# 1-Schematic_5G23_copy.net
KiCad netlist of a schematic drawn in EasyEDA
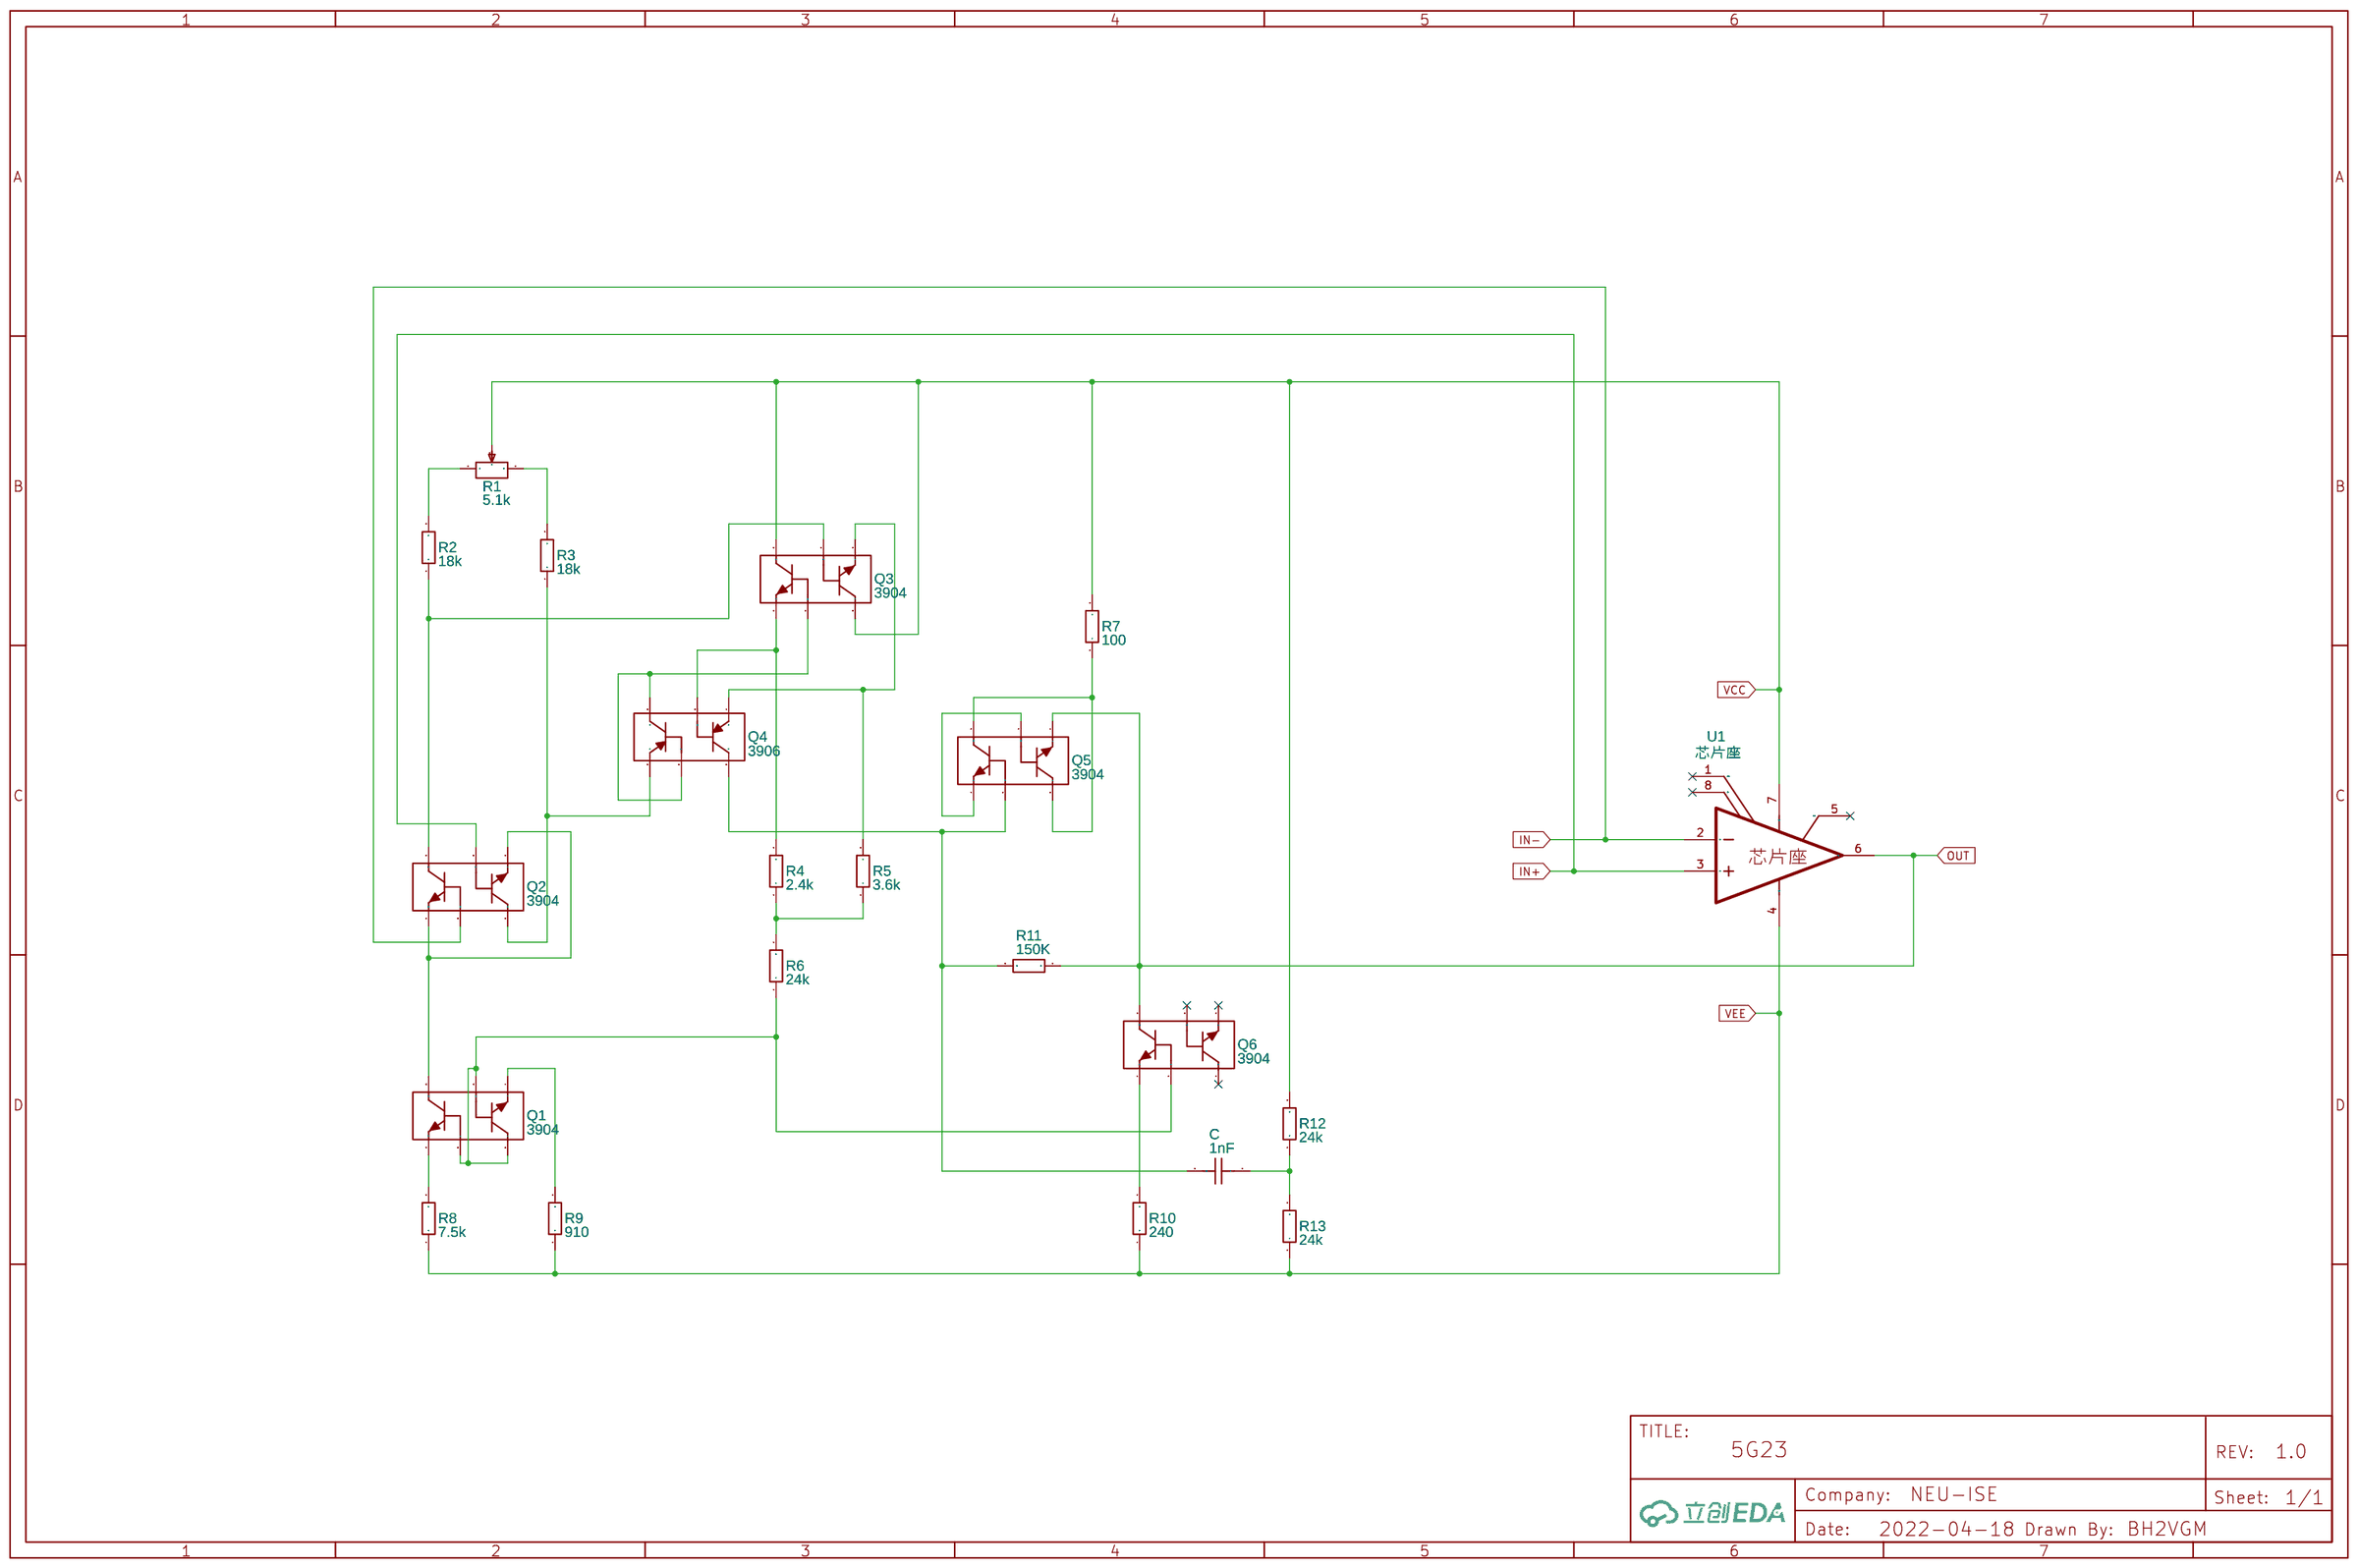
[diagram p0: schematic sheet]

(export (version "E")
  (design (tool "Eeschema 10.0.6"))
  (components
    (comp (ref "C")
      (value "1nF")
      (fields
        (field (name "BOM_Manufacturer Part") "1nF-C0603")
        (field (name "BOM_Supplier Part") "C2940049")
      )
      (libsource (lib "") (part "1NF-C0603"))
    )
    (comp (ref "Q1")
      (value "3904")
      (fields
        (field (name "BOM_Manufacturer Part") "MMDT3904-7-F")
        (field (name "BOM_Supplier Part") "C83572")
      )
      (libsource (lib "") (part "MMDT3904"))
    )
    (comp (ref "Q2")
      (value "3904")
      (fields
        (field (name "BOM_Manufacturer Part") "MMDT3904-7-F")
        (field (name "BOM_Supplier Part") "C83572")
      )
      (libsource (lib "") (part "MMDT3904"))
    )
    (comp (ref "Q3")
      (value "3904")
      (fields
        (field (name "BOM_Manufacturer Part") "MMDT3904-7-F")
        (field (name "BOM_Supplier Part") "C83572")
      )
      (libsource (lib "") (part "MMDT3904"))
    )
    (comp (ref "Q4")
      (value "3906")
      (fields
        (field (name "BOM_Manufacturer Part") "MMDT3906-TP")
        (field (name "BOM_Supplier Part") "C779248")
      )
      (libsource (lib "") (part "MMDT3906"))
    )
    (comp (ref "Q5")
      (value "3904")
      (fields
        (field (name "BOM_Manufacturer Part") "MMDT3904-7-F")
        (field (name "BOM_Supplier Part") "C83572")
      )
      (libsource (lib "") (part "MMDT3904"))
    )
    (comp (ref "Q6")
      (value "3904")
      (fields
        (field (name "BOM_Manufacturer Part") "MMDT3904-7-F")
        (field (name "BOM_Supplier Part") "C83572")
      )
      (libsource (lib "") (part "MMDT3904"))
    )
    (comp (ref "R1")
      (value "5.1k")
      (fields
        (field (name "BOM_Manufacturer Part") "VG039NCHXTB204")
        (field (name "BOM_Supplier Part") "C128551")
      )
      (libsource (lib "") (part "VG039NCHXTB204"))
    )
    (comp (ref "R2")
      (value "18k")
      (fields (field (name "BOM_Manufacturer Part") "0805") (field (name "BOM_Supplier Part") "C9900012715"))
      (libsource (lib "") (part "0805"))
    )
    (comp (ref "R3")
      (value "18k")
      (fields (field (name "BOM_Manufacturer Part") "0805") (field (name "BOM_Supplier Part") "C9900012715"))
      (libsource (lib "") (part "0805"))
    )
    (comp (ref "R4")
      (value "2.4k")
      (fields (field (name "BOM_Manufacturer Part") "0805") (field (name "BOM_Supplier Part") "C9900012715"))
      (libsource (lib "") (part "0805"))
    )
    (comp (ref "R5")
      (value "3.6k")
      (fields (field (name "BOM_Manufacturer Part") "0805") (field (name "BOM_Supplier Part") "C9900012715"))
      (libsource (lib "") (part "0805"))
    )
    (comp (ref "R6")
      (value "24k")
      (fields (field (name "BOM_Manufacturer Part") "0805") (field (name "BOM_Supplier Part") "C9900012715"))
      (libsource (lib "") (part "0805"))
    )
    (comp (ref "R7")
      (value "100")
      (fields (field (name "BOM_Manufacturer Part") "0805") (field (name "BOM_Supplier Part") "C9900012715"))
      (libsource (lib "") (part "0805"))
    )
    (comp (ref "R8")
      (value "7.5k")
      (fields (field (name "BOM_Manufacturer Part") "0805") (field (name "BOM_Supplier Part") "C9900012715"))
      (libsource (lib "") (part "0805"))
    )
    (comp (ref "R9")
      (value "910")
      (fields (field (name "BOM_Manufacturer Part") "0805") (field (name "BOM_Supplier Part") "C9900012715"))
      (libsource (lib "") (part "0805"))
    )
    (comp (ref "R10")
      (value "240")
      (fields (field (name "BOM_Manufacturer Part") "0805") (field (name "BOM_Supplier Part") "C9900012715"))
      (libsource (lib "") (part "0805"))
    )
    (comp (ref "R11")
      (value "150K")
      (fields (field (name "BOM_Manufacturer Part") "0805") (field (name "BOM_Supplier Part") "C9900012715"))
      (libsource (lib "") (part "0805_1"))
    )
    (comp (ref "R12")
      (value "24k")
      (fields (field (name "BOM_Manufacturer Part") "0805") (field (name "BOM_Supplier Part") "C9900012715"))
      (libsource (lib "") (part "0805"))
    )
    (comp (ref "R13")
      (value "24k")
      (fields (field (name "BOM_Manufacturer Part") "0805") (field (name "BOM_Supplier Part") "C9900012715"))
      (libsource (lib "") (part "0805"))
    )
    (comp (ref "U1")
      (value "芯片座")
      (fields (field (name "BOM_Manufacturer Part") "UA741CDR") (field (name "BOM_Supplier Part") "C2057458"))
      (libsource (lib "") (part "UA741CP"))
    )
  )
  (nets
    (net (code "1") (name "IN+") (class "Default")
      (node (ref "Q2") (pin "5") (pinfunction "B_5") (pintype "unspecified"))
      (node (ref "U1") (pin "3") (pinfunction "+IN_3") (pintype "unspecified"))
    )
    (net (code "2") (name "IN-") (class "Default")
      (node (ref "Q2") (pin "2") (pinfunction "B_2") (pintype "unspecified"))
      (node (ref "U1") (pin "2") (pinfunction "-IN_2") (pintype "unspecified"))
    )
    (net (code "3") (name "Net-(C-Pad1)") (class "Default")
      (node (ref "C") (pin "1") (pinfunction "1_1") (pintype "unspecified"))
      (node (ref "Q4") (pin "3") (pinfunction "C_3") (pintype "unspecified"))
      (node (ref "Q5") (pin "2") (pinfunction "B_2") (pintype "unspecified"))
      (node (ref "R11") (pin "2") (pinfunction "2_2") (pintype "unspecified"))
    )
    (net (code "4") (name "Net-(C-Pad2)") (class "Default")
      (node (ref "C") (pin "2") (pinfunction "2_2") (pintype "unspecified"))
      (node (ref "R12") (pin "1") (pinfunction "1_1") (pintype "unspecified"))
      (node (ref "R13") (pin "2") (pinfunction "2_2") (pintype "unspecified"))
    )
    (net (code "5") (name "Net-(Q1-B-Pad2)") (class "Default")
      (node (ref "Q1") (pin "2") (pinfunction "B_2") (pintype "unspecified"))
      (node (ref "Q1") (pin "3") (pinfunction "C_3") (pintype "unspecified"))
      (node (ref "Q1") (pin "5") (pinfunction "B_5") (pintype "unspecified"))
      (node (ref "Q6") (pin "2") (pinfunction "B_2") (pintype "unspecified"))
      (node (ref "R6") (pin "1") (pinfunction "1_1") (pintype "unspecified"))
    )
    (net (code "6") (name "Net-(Q1-C-Pad6)") (class "Default")
      (node (ref "Q1") (pin "6") (pinfunction "C_6") (pintype "unspecified"))
      (node (ref "Q2") (pin "1") (pinfunction "E_1") (pintype "unspecified"))
      (node (ref "Q2") (pin "4") (pinfunction "E_4") (pintype "unspecified"))
    )
    (net (code "7") (name "Net-(Q1-E-Pad1)") (class "Default")
      (node (ref "Q1") (pin "1") (pinfunction "E_1") (pintype "unspecified"))
      (node (ref "R8") (pin "2") (pinfunction "2_2") (pintype "unspecified"))
    )
    (net (code "8") (name "Net-(Q1-E-Pad4)") (class "Default")
      (node (ref "Q1") (pin "4") (pinfunction "E_4") (pintype "unspecified"))
      (node (ref "R9") (pin "2") (pinfunction "2_2") (pintype "unspecified"))
    )
    (net (code "9") (name "Net-(Q2-C-Pad3)") (class "Default")
      (node (ref "Q2") (pin "3") (pinfunction "C_3") (pintype "unspecified"))
      (node (ref "Q4") (pin "1") (pinfunction "E_1") (pintype "unspecified"))
      (node (ref "R3") (pin "1") (pinfunction "1_1") (pintype "unspecified"))
    )
    (net (code "10") (name "Net-(Q2-C-Pad6)") (class "Default")
      (node (ref "Q2") (pin "6") (pinfunction "C_6") (pintype "unspecified"))
      (node (ref "Q3") (pin "5") (pinfunction "B_5") (pintype "unspecified"))
      (node (ref "R2") (pin "1") (pinfunction "1_1") (pintype "unspecified"))
    )
    (net (code "11") (name "Net-(Q3-B-Pad2)") (class "Default")
      (node (ref "Q3") (pin "2") (pinfunction "B_2") (pintype "unspecified"))
      (node (ref "Q4") (pin "2") (pinfunction "B_2") (pintype "unspecified"))
      (node (ref "Q4") (pin "6") (pinfunction "C_6") (pintype "unspecified"))
    )
    (net (code "12") (name "Net-(Q3-E-Pad1)") (class "Default")
      (node (ref "Q3") (pin "1") (pinfunction "E_1") (pintype "unspecified"))
      (node (ref "Q4") (pin "5") (pinfunction "B_5") (pintype "unspecified"))
      (node (ref "R4") (pin "2") (pinfunction "2_2") (pintype "unspecified"))
    )
    (net (code "13") (name "Net-(Q3-E-Pad4)") (class "Default")
      (node (ref "Q3") (pin "4") (pinfunction "E_4") (pintype "unspecified"))
      (node (ref "Q4") (pin "4") (pinfunction "E_4") (pintype "unspecified"))
      (node (ref "R5") (pin "2") (pinfunction "2_2") (pintype "unspecified"))
    )
    (net (code "14") (name "Net-(Q5-B-Pad5)") (class "Default")
      (node (ref "Q5") (pin "1") (pinfunction "E_1") (pintype "unspecified"))
      (node (ref "Q5") (pin "5") (pinfunction "B_5") (pintype "unspecified"))
    )
    (net (code "15") (name "Net-(Q5-C-Pad3)") (class "Default")
      (node (ref "Q5") (pin "3") (pinfunction "C_3") (pintype "unspecified"))
      (node (ref "Q5") (pin "6") (pinfunction "C_6") (pintype "unspecified"))
      (node (ref "R7") (pin "1") (pinfunction "1_1") (pintype "unspecified"))
    )
    (net (code "16") (name "Net-(Q6-E-Pad1)") (class "Default")
      (node (ref "Q6") (pin "1") (pinfunction "E_1") (pintype "unspecified"))
      (node (ref "R10") (pin "2") (pinfunction "2_2") (pintype "unspecified"))
    )
    (net (code "17") (name "Net-(R1-Pad1)") (class "Default")
      (node (ref "R1") (pin "1") (pinfunction "1_1") (pintype "input"))
      (node (ref "R2") (pin "2") (pinfunction "2_2") (pintype "unspecified"))
    )
    (net (code "18") (name "Net-(R1-Pad3)") (class "Default")
      (node (ref "R1") (pin "3") (pinfunction "3_3") (pintype "input"))
      (node (ref "R3") (pin "2") (pinfunction "2_2") (pintype "unspecified"))
    )
    (net (code "19") (name "Net-(R4-Pad1)") (class "Default")
      (node (ref "R4") (pin "1") (pinfunction "1_1") (pintype "unspecified"))
      (node (ref "R5") (pin "1") (pinfunction "1_1") (pintype "unspecified"))
      (node (ref "R6") (pin "2") (pinfunction "2_2") (pintype "unspecified"))
    )
    (net (code "20") (name "OUT") (class "Default")
      (node (ref "Q5") (pin "4") (pinfunction "E_4") (pintype "unspecified"))
      (node (ref "Q6") (pin "6") (pinfunction "C_6") (pintype "unspecified"))
      (node (ref "R11") (pin "1") (pinfunction "1_1") (pintype "unspecified"))
      (node (ref "U1") (pin "6") (pinfunction "OUT_6") (pintype "output"))
    )
    (net (code "21") (name "VCC") (class "Default")
      (node (ref "Q3") (pin "3") (pinfunction "C_3") (pintype "unspecified"))
      (node (ref "Q3") (pin "6") (pinfunction "C_6") (pintype "unspecified"))
      (node (ref "R1") (pin "2") (pinfunction "2_2") (pintype "input"))
      (node (ref "R12") (pin "2") (pinfunction "2_2") (pintype "unspecified"))
      (node (ref "R7") (pin "2") (pinfunction "2_2") (pintype "unspecified"))
      (node (ref "U1") (pin "7") (pinfunction "VCC+_7") (pintype "passive"))
    )
    (net (code "22") (name "VEE") (class "Default")
      (node (ref "R10") (pin "1") (pinfunction "1_1") (pintype "unspecified"))
      (node (ref "R13") (pin "1") (pinfunction "1_1") (pintype "unspecified"))
      (node (ref "R8") (pin "1") (pinfunction "1_1") (pintype "unspecified"))
      (node (ref "R9") (pin "1") (pinfunction "1_1") (pintype "unspecified"))
      (node (ref "U1") (pin "4") (pinfunction "VCC-_4") (pintype "passive"))
    )
    (net (code "23") (name "unconnected-(Q6-B-Pad5)") (class "Default")
      (node (ref "Q6") (pin "5") (pinfunction "B_5") (pintype "unspecified+no_connect"))
    )
    (net (code "24") (name "unconnected-(Q6-C-Pad3)") (class "Default")
      (node (ref "Q6") (pin "3") (pinfunction "C_3") (pintype "unspecified+no_connect"))
    )
    (net (code "25") (name "unconnected-(Q6-E-Pad4)") (class "Default")
      (node (ref "Q6") (pin "4") (pinfunction "E_4") (pintype "unspecified+no_connect"))
    )
    (net (code "26") (name "unconnected-(U1-NC-Pad8)") (class "Default")
      (node (ref "U1") (pin "8") (pinfunction "NC_8") (pintype "unspecified+no_connect"))
    )
    (net (code "27") (name "unconnected-(U1-OFFSET_N1-Pad1)") (class "Default")
      (node (ref "U1") (pin "1") (pinfunction "OFFSET_N1_1") (pintype "unspecified+no_connect"))
    )
    (net (code "28") (name "unconnected-(U1-OFFSET_N2-Pad5)") (class "Default")
      (node (ref "U1") (pin "5") (pinfunction "OFFSET_N2_5") (pintype "unspecified+no_connect"))
    )
  )
)
